# Motor_Powerboard_Schematic_1A.net
KiCad netlist of a schematic drawn in EAGLE
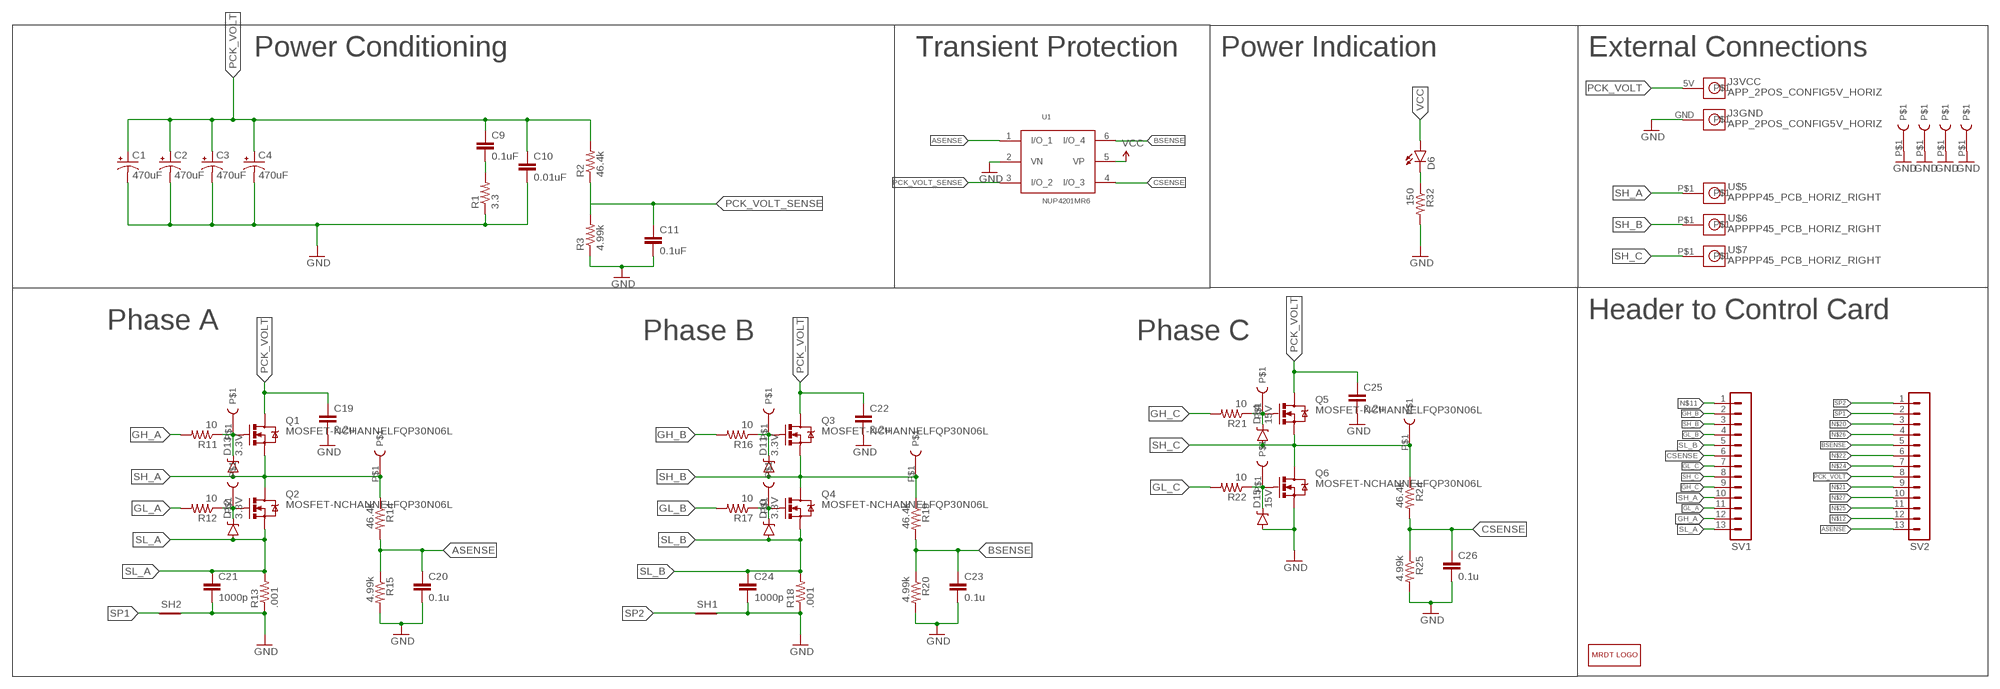
[diagram p0: schematic, sheet 1]

(export (version "E")
  (design (tool "Eeschema 10.0.6"))
  (components
    (comp (ref "C1")
      (value "470uF")
      (footprint "eagle-import:CPOL-RADIAL-1000UF-25V")
      (libsource (lib "eagle-import") (part "CAP_POLPTH4"))
    )
    (comp (ref "C2")
      (value "470uF")
      (footprint "eagle-import:CPOL-RADIAL-1000UF-25V")
      (libsource (lib "eagle-import") (part "CAP_POLPTH4"))
    )
    (comp (ref "C3")
      (value "470uF")
      (footprint "eagle-import:CPOL-RADIAL-1000UF-25V")
      (libsource (lib "eagle-import") (part "CAP_POLPTH4"))
    )
    (comp (ref "C4")
      (value "470uF")
      (footprint "eagle-import:CPOL-RADIAL-1000UF-25V")
      (libsource (lib "eagle-import") (part "CAP_POLPTH4"))
    )
    (comp (ref "C9")
      (value "0.1uF")
      (footprint "eagle-import:0805")
      (libsource (lib "eagle-import") (part "CAP0805"))
    )
    (comp (ref "C10")
      (value "0.01uF")
      (footprint "eagle-import:0805")
      (libsource (lib "eagle-import") (part "CAP0805"))
    )
    (comp (ref "C11")
      (value "0.1uF")
      (footprint "eagle-import:0805")
      (libsource (lib "eagle-import") (part "CAP0805"))
    )
    (comp (ref "C19")
      (value "2.2u")
      (footprint "eagle-import:1206")
      (libsource (lib "eagle-import") (part "CAP1206"))
    )
    (comp (ref "C20")
      (value "0.1u")
      (footprint "eagle-import:0805")
      (libsource (lib "eagle-import") (part "CAP0805"))
    )
    (comp (ref "C21")
      (value "1000p")
      (footprint "eagle-import:0805")
      (libsource (lib "eagle-import") (part "CAP0805"))
    )
    (comp (ref "C22")
      (value "2.2u")
      (footprint "eagle-import:1206")
      (libsource (lib "eagle-import") (part "CAP1206"))
    )
    (comp (ref "C23")
      (value "0.1u")
      (footprint "eagle-import:0805")
      (libsource (lib "eagle-import") (part "CAP0805"))
    )
    (comp (ref "C24")
      (value "1000p")
      (footprint "eagle-import:0805")
      (libsource (lib "eagle-import") (part "CAP0805"))
    )
    (comp (ref "C25")
      (value "2.2u")
      (footprint "eagle-import:1206")
      (libsource (lib "eagle-import") (part "CAP1206"))
    )
    (comp (ref "C26")
      (value "0.1u")
      (footprint "eagle-import:0805")
      (libsource (lib "eagle-import") (part "CAP0805"))
    )
    (comp (ref "D6")
      (value "LED1206")
      (footprint "eagle-import:LED-1206")
      (libsource (lib "eagle-import") (part "LED1206"))
    )
    (comp (ref "D10")
      (value "3.3V")
      (footprint "eagle-import:SOD-323")
      (libsource (lib "eagle-import") (part "DIODE-ZENER3.3V"))
    )
    (comp (ref "D11")
      (value "3.3V")
      (footprint "eagle-import:SOD-323")
      (libsource (lib "eagle-import") (part "DIODE-ZENER3.3V"))
    )
    (comp (ref "D12")
      (value "3.3V")
      (footprint "eagle-import:SOD-323")
      (libsource (lib "eagle-import") (part "DIODE-ZENER3.3V"))
    )
    (comp (ref "D13")
      (value "3.3V")
      (footprint "eagle-import:SOD-323")
      (libsource (lib "eagle-import") (part "DIODE-ZENER3.3V"))
    )
    (comp (ref "D14")
      (value "15V")
      (footprint "eagle-import:SOD-323")
      (libsource (lib "eagle-import") (part "DIODE-ZENER3.3V"))
    )
    (comp (ref "D15")
      (value "15V")
      (footprint "eagle-import:SOD-323")
      (libsource (lib "eagle-import") (part "DIODE-ZENER3.3V"))
    )
    (comp (ref "J3")
      (value "APP_2POS_CONFIG5V_HORIZ")
      (footprint "eagle-import:APP45_5V_HORIZ_CONFIG")
      (libsource (lib "eagle-import") (part "APP_2POS_CONFIG5V_HORIZ"))
    )
    (comp (ref "LOGO1")
      (value "MRDT_LOGO")
      (footprint "eagle-import:MRDT_LOGO")
      (libsource (lib "eagle-import") (part "MRDT_LOGO"))
    )
    (comp (ref "Q1")
      (value "MOSFET-NCHANNELFQP30N06L")
      (footprint "eagle-import:TO220V")
      (libsource (lib "eagle-import") (part "MOSFET-NCHANNELFQP30N06L"))
    )
    (comp (ref "Q2")
      (value "MOSFET-NCHANNELFQP30N06L")
      (footprint "eagle-import:TO220V")
      (libsource (lib "eagle-import") (part "MOSFET-NCHANNELFQP30N06L"))
    )
    (comp (ref "Q3")
      (value "MOSFET-NCHANNELFQP30N06L")
      (footprint "eagle-import:TO220V")
      (libsource (lib "eagle-import") (part "MOSFET-NCHANNELFQP30N06L"))
    )
    (comp (ref "Q4")
      (value "MOSFET-NCHANNELFQP30N06L")
      (footprint "eagle-import:TO220V")
      (libsource (lib "eagle-import") (part "MOSFET-NCHANNELFQP30N06L"))
    )
    (comp (ref "Q5")
      (value "MOSFET-NCHANNELFQP30N06L")
      (footprint "eagle-import:TO220V")
      (libsource (lib "eagle-import") (part "MOSFET-NCHANNELFQP30N06L"))
    )
    (comp (ref "Q6")
      (value "MOSFET-NCHANNELFQP30N06L")
      (footprint "eagle-import:TO220V")
      (libsource (lib "eagle-import") (part "MOSFET-NCHANNELFQP30N06L"))
    )
    (comp (ref "R1")
      (value "3.3")
      (footprint "eagle-import:1206")
      (libsource (lib "eagle-import") (part "RESISTOR1206"))
    )
    (comp (ref "R2")
      (value "46.4k")
      (footprint "eagle-import:0805")
      (libsource (lib "eagle-import") (part "RESISTOR0805-RES"))
    )
    (comp (ref "R3")
      (value "4.99k")
      (footprint "eagle-import:0805")
      (libsource (lib "eagle-import") (part "RESISTOR0805-RES"))
    )
    (comp (ref "R11")
      (value "10")
      (footprint "eagle-import:0805")
      (libsource (lib "eagle-import") (part "RESISTOR0805-RES"))
    )
    (comp (ref "R12")
      (value "10")
      (footprint "eagle-import:0805")
      (libsource (lib "eagle-import") (part "RESISTOR0805-RES"))
    )
    (comp (ref "R13")
      (value ".001")
      (footprint "eagle-import:1206")
      (libsource (lib "eagle-import") (part "RESISTOR1206"))
    )
    (comp (ref "R14")
      (value "46.4k")
      (footprint "eagle-import:0805")
      (libsource (lib "eagle-import") (part "RESISTOR0805-RES"))
    )
    (comp (ref "R15")
      (value "4.99k")
      (footprint "eagle-import:0805")
      (libsource (lib "eagle-import") (part "RESISTOR0805-RES"))
    )
    (comp (ref "R16")
      (value "10")
      (footprint "eagle-import:0805")
      (libsource (lib "eagle-import") (part "RESISTOR0805-RES"))
    )
    (comp (ref "R17")
      (value "10")
      (footprint "eagle-import:0805")
      (libsource (lib "eagle-import") (part "RESISTOR0805-RES"))
    )
    (comp (ref "R18")
      (value ".001")
      (footprint "eagle-import:1206")
      (libsource (lib "eagle-import") (part "RESISTOR1206"))
    )
    (comp (ref "R19")
      (value "46.4k")
      (footprint "eagle-import:0805")
      (libsource (lib "eagle-import") (part "RESISTOR0805-RES"))
    )
    (comp (ref "R20")
      (value "4.99k")
      (footprint "eagle-import:0805")
      (libsource (lib "eagle-import") (part "RESISTOR0805-RES"))
    )
    (comp (ref "R21")
      (value "10")
      (footprint "eagle-import:0805")
      (libsource (lib "eagle-import") (part "RESISTOR0805-RES"))
    )
    (comp (ref "R22")
      (value "10")
      (footprint "eagle-import:0805")
      (libsource (lib "eagle-import") (part "RESISTOR0805-RES"))
    )
    (comp (ref "R24")
      (value "46.4k")
      (footprint "eagle-import:0805")
      (libsource (lib "eagle-import") (part "RESISTOR0805-RES"))
    )
    (comp (ref "R25")
      (value "4.99k")
      (footprint "eagle-import:0805")
      (libsource (lib "eagle-import") (part "RESISTOR0805-RES"))
    )
    (comp (ref "R32")
      (value "150")
      (footprint "eagle-import:0805")
      (libsource (lib "eagle-import") (part "RESISTOR0805-RES"))
    )
    (comp (ref "SH1")
      (value "SHORT-HT5")
      (footprint "eagle-import:SHORT_TOP-50")
      (libsource (lib "eagle-import") (part "SHORT-HT5"))
    )
    (comp (ref "SH2")
      (value "SHORT-HT5")
      (footprint "eagle-import:SHORT_TOP-50")
      (libsource (lib "eagle-import") (part "SHORT-HT5"))
    )
    (comp (ref "SV1")
      (value "MA13-1")
      (footprint "eagle-import:MA13-1")
      (libsource (lib "eagle-import") (part "MA13-1"))
    )
    (comp (ref "SV2")
      (value "MA13-1")
      (footprint "eagle-import:MA13-1")
      (libsource (lib "eagle-import") (part "MA13-1"))
    )
    (comp (ref "U$5")
      (value "APPPP45_PCB_HORIZ_RIGHT")
      (footprint "eagle-import:APP45_PCB_HORIZ_RIGHT")
      (libsource (lib "eagle-import") (part "APPPP45_PCB_HORIZ_RIGHT"))
    )
    (comp (ref "U$6")
      (value "APPPP45_PCB_HORIZ_RIGHT")
      (footprint "eagle-import:APP45_PCB_HORIZ_RIGHT")
      (libsource (lib "eagle-import") (part "APPPP45_PCB_HORIZ_RIGHT"))
    )
    (comp (ref "U$7")
      (value "APPPP45_PCB_HORIZ_RIGHT")
      (footprint "eagle-import:APP45_PCB_HORIZ_RIGHT")
      (libsource (lib "eagle-import") (part "APPPP45_PCB_HORIZ_RIGHT"))
    )
    (comp (ref "U$12")
      (value "TEST_POINT_0.1INDIAM")
      (footprint "eagle-import:TEST_POINT_0.1INDIAM")
      (libsource (lib "eagle-import") (part "TEST_POINT_0.1INDIAM"))
    )
    (comp (ref "U$15")
      (value "TEST_POINT_0.1INDIAM")
      (footprint "eagle-import:TEST_POINT_0.1INDIAM")
      (libsource (lib "eagle-import") (part "TEST_POINT_0.1INDIAM"))
    )
    (comp (ref "U$16")
      (value "TEST_POINT_0.1INDIAM")
      (footprint "eagle-import:TEST_POINT_0.1INDIAM")
      (libsource (lib "eagle-import") (part "TEST_POINT_0.1INDIAM"))
    )
    (comp (ref "U$17")
      (value "TEST_POINT_0.1INDIAM")
      (footprint "eagle-import:TEST_POINT_0.1INDIAM")
      (libsource (lib "eagle-import") (part "TEST_POINT_0.1INDIAM"))
    )
    (comp (ref "U$18")
      (value "TEST_POINT_0.1INDIAM")
      (footprint "eagle-import:TEST_POINT_0.1INDIAM")
      (libsource (lib "eagle-import") (part "TEST_POINT_0.1INDIAM"))
    )
    (comp (ref "U$19")
      (value "TEST_POINT_0.1INDIAM")
      (footprint "eagle-import:TEST_POINT_0.1INDIAM")
      (libsource (lib "eagle-import") (part "TEST_POINT_0.1INDIAM"))
    )
    (comp (ref "U$20")
      (value "TEST_POINT_0.1INDIAM")
      (footprint "eagle-import:TEST_POINT_0.1INDIAM")
      (libsource (lib "eagle-import") (part "TEST_POINT_0.1INDIAM"))
    )
    (comp (ref "U$24")
      (value "TEST_POINT_0.1INDIAM")
      (footprint "eagle-import:TEST_POINT_0.1INDIAM")
      (libsource (lib "eagle-import") (part "TEST_POINT_0.1INDIAM"))
    )
    (comp (ref "U$25")
      (value "TEST_POINT_0.1INDIAM")
      (footprint "eagle-import:TEST_POINT_0.1INDIAM")
      (libsource (lib "eagle-import") (part "TEST_POINT_0.1INDIAM"))
    )
    (comp (ref "U$26")
      (value "TEST_POINT_0.1INDIAM")
      (footprint "eagle-import:TEST_POINT_0.1INDIAM")
      (libsource (lib "eagle-import") (part "TEST_POINT_0.1INDIAM"))
    )
    (comp (ref "U$27")
      (value "TEST_POINT_0.1INDIAM")
      (footprint "eagle-import:TEST_POINT_0.1INDIAM")
      (libsource (lib "eagle-import") (part "TEST_POINT_0.1INDIAM"))
    )
    (comp (ref "U$28")
      (value "TEST_POINT_0.1INDIAM")
      (footprint "eagle-import:TEST_POINT_0.1INDIAM")
      (libsource (lib "eagle-import") (part "TEST_POINT_0.1INDIAM"))
    )
    (comp (ref "U$29")
      (value "TEST_POINT_0.1INDIAM")
      (footprint "eagle-import:TEST_POINT_0.1INDIAM")
      (libsource (lib "eagle-import") (part "TEST_POINT_0.1INDIAM"))
    )
    (comp (ref "U1")
      (value "NUP4201MR6")
      (footprint "eagle-import:TSOP-6")
      (libsource (lib "eagle-import") (part "NUP4201MR6"))
    )
  )
  (nets
    (net (code "1") (name "ASENSE") (class "Default")
      (node (ref "C20") (pin "1") (pinfunction "1_1") (pintype "passive"))
      (node (ref "R14") (pin "2") (pinfunction "2_2") (pintype "passive"))
      (node (ref "R15") (pin "1") (pinfunction "1_1") (pintype "passive"))
      (node (ref "SV2") (pin "13") (pinfunction "13_13") (pintype "passive"))
      (node (ref "U1") (pin "1") (pinfunction "I/O_1_1") (pintype "bidirectional"))
    )
    (net (code "2") (name "BSENSE") (class "Default")
      (node (ref "C23") (pin "1") (pinfunction "1_1") (pintype "passive"))
      (node (ref "R19") (pin "2") (pinfunction "2_2") (pintype "passive"))
      (node (ref "R20") (pin "1") (pinfunction "1_1") (pintype "passive"))
      (node (ref "SV2") (pin "5") (pinfunction "5_5") (pintype "passive"))
      (node (ref "U1") (pin "6") (pinfunction "I/O_4_6") (pintype "bidirectional"))
    )
    (net (code "3") (name "CSENSE") (class "Default")
      (node (ref "C26") (pin "1") (pinfunction "1_1") (pintype "passive"))
      (node (ref "R24") (pin "2") (pinfunction "2_2") (pintype "passive"))
      (node (ref "R25") (pin "1") (pinfunction "1_1") (pintype "passive"))
      (node (ref "SV1") (pin "6") (pinfunction "6_6") (pintype "passive"))
      (node (ref "U1") (pin "4") (pinfunction "I/O_3_4") (pintype "bidirectional"))
    )
    (net (code "4") (name "GH_A") (class "Default")
      (node (ref "R11") (pin "2") (pinfunction "2_2") (pintype "passive"))
      (node (ref "SV1") (pin "12") (pinfunction "12_12") (pintype "passive"))
    )
    (net (code "5") (name "GH_B") (class "Default")
      (node (ref "R16") (pin "2") (pinfunction "2_2") (pintype "passive"))
      (node (ref "SV1") (pin "2") (pinfunction "2_2") (pintype "passive"))
    )
    (net (code "6") (name "GH_C") (class "Default")
      (node (ref "R21") (pin "2") (pinfunction "2_2") (pintype "passive"))
      (node (ref "SV1") (pin "9") (pinfunction "9_9") (pintype "passive"))
    )
    (net (code "7") (name "GL_A") (class "Default")
      (node (ref "R12") (pin "2") (pinfunction "2_2") (pintype "passive"))
      (node (ref "SV1") (pin "11") (pinfunction "11_11") (pintype "passive"))
    )
    (net (code "8") (name "GL_B") (class "Default")
      (node (ref "R17") (pin "2") (pinfunction "2_2") (pintype "passive"))
      (node (ref "SV1") (pin "4") (pinfunction "4_4") (pintype "passive"))
    )
    (net (code "9") (name "GL_C") (class "Default")
      (node (ref "R22") (pin "2") (pinfunction "2_2") (pintype "passive"))
      (node (ref "SV1") (pin "7") (pinfunction "7_7") (pintype "passive"))
    )
    (net (code "10") (name "GND") (class "Default")
      (node (ref "C1") (pin "2") (pinfunction "-_2") (pintype "passive"))
      (node (ref "C10") (pin "2") (pinfunction "2_2") (pintype "passive"))
      (node (ref "C11") (pin "2") (pinfunction "2_2") (pintype "passive"))
      (node (ref "C19") (pin "2") (pinfunction "2_2") (pintype "passive"))
      (node (ref "C2") (pin "2") (pinfunction "-_2") (pintype "passive"))
      (node (ref "C20") (pin "2") (pinfunction "2_2") (pintype "passive"))
      (node (ref "C21") (pin "2") (pinfunction "2_2") (pintype "passive"))
      (node (ref "C22") (pin "2") (pinfunction "2_2") (pintype "passive"))
      (node (ref "C23") (pin "2") (pinfunction "2_2") (pintype "passive"))
      (node (ref "C24") (pin "2") (pinfunction "2_2") (pintype "passive"))
      (node (ref "C25") (pin "2") (pinfunction "2_2") (pintype "passive"))
      (node (ref "C26") (pin "2") (pinfunction "2_2") (pintype "passive"))
      (node (ref "C3") (pin "2") (pinfunction "-_2") (pintype "passive"))
      (node (ref "C4") (pin "2") (pinfunction "-_2") (pintype "passive"))
      (node (ref "D15") (pin "A") (pinfunction "A_A") (pintype "passive"))
      (node (ref "J3") (pin "GND") (pinfunction "P$1_GND") (pintype "bidirectional"))
      (node (ref "Q6") (pin "3") (pinfunction "S_3") (pintype "passive"))
      (node (ref "R1") (pin "1") (pinfunction "1_1") (pintype "passive"))
      (node (ref "R13") (pin "1") (pinfunction "1_1") (pintype "passive"))
      (node (ref "R15") (pin "2") (pinfunction "2_2") (pintype "passive"))
      (node (ref "R18") (pin "1") (pinfunction "1_1") (pintype "passive"))
      (node (ref "R20") (pin "2") (pinfunction "2_2") (pintype "passive"))
      (node (ref "R25") (pin "2") (pinfunction "2_2") (pintype "passive"))
      (node (ref "R3") (pin "1") (pinfunction "1_1") (pintype "passive"))
      (node (ref "R32") (pin "2") (pinfunction "2_2") (pintype "passive"))
      (node (ref "SH1") (pin "2") (pinfunction "P$2_2") (pintype "bidirectional"))
      (node (ref "SH2") (pin "2") (pinfunction "P$2_2") (pintype "bidirectional"))
      (node (ref "U$26") (pin "P$1") (pinfunction "P$1_P$1") (pintype "bidirectional"))
      (node (ref "U$27") (pin "P$1") (pinfunction "P$1_P$1") (pintype "bidirectional"))
      (node (ref "U$28") (pin "P$1") (pinfunction "P$1_P$1") (pintype "bidirectional"))
      (node (ref "U$29") (pin "P$1") (pinfunction "P$1_P$1") (pintype "bidirectional"))
      (node (ref "U1") (pin "2") (pinfunction "VN_2") (pintype "bidirectional"))
    )
    (net (code "11") (name "N$11") (class "Default")
      (node (ref "SV1") (pin "1") (pinfunction "1_1") (pintype "passive"))
    )
    (net (code "12") (name "N$12") (class "Default")
      (node (ref "SV2") (pin "12") (pinfunction "12_12") (pintype "passive"))
    )
    (net (code "13") (name "N$20") (class "Default")
      (node (ref "SV2") (pin "3") (pinfunction "3_3") (pintype "passive"))
    )
    (net (code "14") (name "N$21") (class "Default")
      (node (ref "SV2") (pin "9") (pinfunction "9_9") (pintype "passive"))
    )
    (net (code "15") (name "N$22") (class "Default")
      (node (ref "SV2") (pin "6") (pinfunction "6_6") (pintype "passive"))
    )
    (net (code "16") (name "N$24") (class "Default")
      (node (ref "SV2") (pin "7") (pinfunction "7_7") (pintype "passive"))
    )
    (net (code "17") (name "N$25") (class "Default")
      (node (ref "SV2") (pin "11") (pinfunction "11_11") (pintype "passive"))
    )
    (net (code "18") (name "N$26") (class "Default")
      (node (ref "SV2") (pin "4") (pinfunction "4_4") (pintype "passive"))
    )
    (net (code "19") (name "N$27") (class "Default")
      (node (ref "SV2") (pin "10") (pinfunction "10_10") (pintype "passive"))
    )
    (net (code "20") (name "Net-(C9-Pad2)") (class "Default")
      (node (ref "C9") (pin "2") (pinfunction "2_2") (pintype "passive"))
      (node (ref "R1") (pin "2") (pinfunction "2_2") (pintype "passive"))
    )
    (net (code "21") (name "Net-(D6-PadC)") (class "Default")
      (node (ref "D6") (pin "C") (pinfunction "C_C") (pintype "passive"))
      (node (ref "R32") (pin "1") (pinfunction "1_1") (pintype "passive"))
    )
    (net (code "22") (name "Net-(Q1-G)") (class "Default")
      (node (ref "D13") (pin "C") (pinfunction "C_C") (pintype "passive"))
      (node (ref "Q1") (pin "1") (pinfunction "G_1") (pintype "passive"))
      (node (ref "R11") (pin "1") (pinfunction "1_1") (pintype "passive"))
      (node (ref "U$12") (pin "P$1") (pinfunction "P$1_P$1") (pintype "bidirectional"))
    )
    (net (code "23") (name "Net-(Q2-G)") (class "Default")
      (node (ref "D12") (pin "C") (pinfunction "C_C") (pintype "passive"))
      (node (ref "Q2") (pin "1") (pinfunction "G_1") (pintype "passive"))
      (node (ref "R12") (pin "1") (pinfunction "1_1") (pintype "passive"))
      (node (ref "U$15") (pin "P$1") (pinfunction "P$1_P$1") (pintype "bidirectional"))
    )
    (net (code "24") (name "Net-(Q3-G)") (class "Default")
      (node (ref "D11") (pin "C") (pinfunction "C_C") (pintype "passive"))
      (node (ref "Q3") (pin "1") (pinfunction "G_1") (pintype "passive"))
      (node (ref "R16") (pin "1") (pinfunction "1_1") (pintype "passive"))
      (node (ref "U$16") (pin "P$1") (pinfunction "P$1_P$1") (pintype "bidirectional"))
    )
    (net (code "25") (name "Net-(Q4-G)") (class "Default")
      (node (ref "D10") (pin "C") (pinfunction "C_C") (pintype "passive"))
      (node (ref "Q4") (pin "1") (pinfunction "G_1") (pintype "passive"))
      (node (ref "R17") (pin "1") (pinfunction "1_1") (pintype "passive"))
      (node (ref "U$17") (pin "P$1") (pinfunction "P$1_P$1") (pintype "bidirectional"))
    )
    (net (code "26") (name "Net-(Q5-G)") (class "Default")
      (node (ref "D14") (pin "C") (pinfunction "C_C") (pintype "passive"))
      (node (ref "Q5") (pin "1") (pinfunction "G_1") (pintype "passive"))
      (node (ref "R21") (pin "1") (pinfunction "1_1") (pintype "passive"))
      (node (ref "U$18") (pin "P$1") (pinfunction "P$1_P$1") (pintype "bidirectional"))
    )
    (net (code "27") (name "Net-(Q6-G)") (class "Default")
      (node (ref "D15") (pin "C") (pinfunction "C_C") (pintype "passive"))
      (node (ref "Q6") (pin "1") (pinfunction "G_1") (pintype "passive"))
      (node (ref "R22") (pin "1") (pinfunction "1_1") (pintype "passive"))
      (node (ref "U$19") (pin "P$1") (pinfunction "P$1_P$1") (pintype "bidirectional"))
    )
    (net (code "28") (name "PCK_VOLT") (class "Default")
      (node (ref "C1") (pin "1") (pinfunction "+_1") (pintype "passive"))
      (node (ref "C10") (pin "1") (pinfunction "1_1") (pintype "passive"))
      (node (ref "C19") (pin "1") (pinfunction "1_1") (pintype "passive"))
      (node (ref "C2") (pin "1") (pinfunction "+_1") (pintype "passive"))
      (node (ref "C22") (pin "1") (pinfunction "1_1") (pintype "passive"))
      (node (ref "C25") (pin "1") (pinfunction "1_1") (pintype "passive"))
      (node (ref "C3") (pin "1") (pinfunction "+_1") (pintype "passive"))
      (node (ref "C4") (pin "1") (pinfunction "+_1") (pintype "passive"))
      (node (ref "C9") (pin "1") (pinfunction "1_1") (pintype "passive"))
      (node (ref "J3") (pin "5V") (pinfunction "P$1_5V") (pintype "bidirectional"))
      (node (ref "Q1") (pin "2") (pinfunction "D_2") (pintype "passive"))
      (node (ref "Q3") (pin "2") (pinfunction "D_2") (pintype "passive"))
      (node (ref "Q5") (pin "2") (pinfunction "D_2") (pintype "passive"))
      (node (ref "R2") (pin "2") (pinfunction "2_2") (pintype "passive"))
      (node (ref "SV2") (pin "8") (pinfunction "8_8") (pintype "passive"))
    )
    (net (code "29") (name "PCK_VOLT_SENSE") (class "Default")
      (node (ref "C11") (pin "1") (pinfunction "1_1") (pintype "passive"))
      (node (ref "R2") (pin "1") (pinfunction "1_1") (pintype "passive"))
      (node (ref "R3") (pin "2") (pinfunction "2_2") (pintype "passive"))
      (node (ref "U1") (pin "3") (pinfunction "I/O_2_3") (pintype "bidirectional"))
    )
    (net (code "30") (name "SH_A") (class "Default")
      (node (ref "D13") (pin "A") (pinfunction "A_A") (pintype "passive"))
      (node (ref "Q1") (pin "3") (pinfunction "S_3") (pintype "passive"))
      (node (ref "Q2") (pin "2") (pinfunction "D_2") (pintype "passive"))
      (node (ref "R14") (pin "1") (pinfunction "1_1") (pintype "passive"))
      (node (ref "SV1") (pin "10") (pinfunction "10_10") (pintype "passive"))
      (node (ref "U$25") (pin "P$1") (pinfunction "P$1_P$1") (pintype "bidirectional"))
      (node (ref "U$5") (pin "P$1") (pinfunction "P$1_P$1") (pintype "bidirectional"))
    )
    (net (code "31") (name "SH_B") (class "Default")
      (node (ref "D11") (pin "A") (pinfunction "A_A") (pintype "passive"))
      (node (ref "Q3") (pin "3") (pinfunction "S_3") (pintype "passive"))
      (node (ref "Q4") (pin "2") (pinfunction "D_2") (pintype "passive"))
      (node (ref "R19") (pin "1") (pinfunction "1_1") (pintype "passive"))
      (node (ref "SV1") (pin "3") (pinfunction "3_3") (pintype "passive"))
      (node (ref "U$24") (pin "P$1") (pinfunction "P$1_P$1") (pintype "bidirectional"))
      (node (ref "U$6") (pin "P$1") (pinfunction "P$1_P$1") (pintype "bidirectional"))
    )
    (net (code "32") (name "SH_C") (class "Default")
      (node (ref "D14") (pin "A") (pinfunction "A_A") (pintype "passive"))
      (node (ref "Q5") (pin "3") (pinfunction "S_3") (pintype "passive"))
      (node (ref "Q6") (pin "2") (pinfunction "D_2") (pintype "passive"))
      (node (ref "R24") (pin "1") (pinfunction "1_1") (pintype "passive"))
      (node (ref "SV1") (pin "8") (pinfunction "8_8") (pintype "passive"))
      (node (ref "U$20") (pin "P$1") (pinfunction "P$1_P$1") (pintype "bidirectional"))
      (node (ref "U$7") (pin "P$1") (pinfunction "P$1_P$1") (pintype "bidirectional"))
    )
    (net (code "33") (name "SL_A") (class "Default")
      (node (ref "C21") (pin "1") (pinfunction "1_1") (pintype "passive"))
      (node (ref "D12") (pin "A") (pinfunction "A_A") (pintype "passive"))
      (node (ref "Q2") (pin "3") (pinfunction "S_3") (pintype "passive"))
      (node (ref "R13") (pin "2") (pinfunction "2_2") (pintype "passive"))
      (node (ref "SV1") (pin "13") (pinfunction "13_13") (pintype "passive"))
    )
    (net (code "34") (name "SL_B") (class "Default")
      (node (ref "C24") (pin "1") (pinfunction "1_1") (pintype "passive"))
      (node (ref "D10") (pin "A") (pinfunction "A_A") (pintype "passive"))
      (node (ref "Q4") (pin "3") (pinfunction "S_3") (pintype "passive"))
      (node (ref "R18") (pin "2") (pinfunction "2_2") (pintype "passive"))
      (node (ref "SV1") (pin "5") (pinfunction "5_5") (pintype "passive"))
    )
    (net (code "35") (name "SP1") (class "Default")
      (node (ref "SH2") (pin "1") (pinfunction "P$1_1") (pintype "bidirectional"))
      (node (ref "SV2") (pin "2") (pinfunction "2_2") (pintype "passive"))
    )
    (net (code "36") (name "SP2") (class "Default")
      (node (ref "SH1") (pin "1") (pinfunction "P$1_1") (pintype "bidirectional"))
      (node (ref "SV2") (pin "1") (pinfunction "1_1") (pintype "passive"))
    )
    (net (code "37") (name "VCC") (class "Default")
      (node (ref "D6") (pin "A") (pinfunction "A_A") (pintype "passive"))
      (node (ref "U1") (pin "5") (pinfunction "VP_5") (pintype "bidirectional"))
    )
  )
)
